# DongHoInternet.net
KiCad netlist of a schematic drawn in Altium Designer
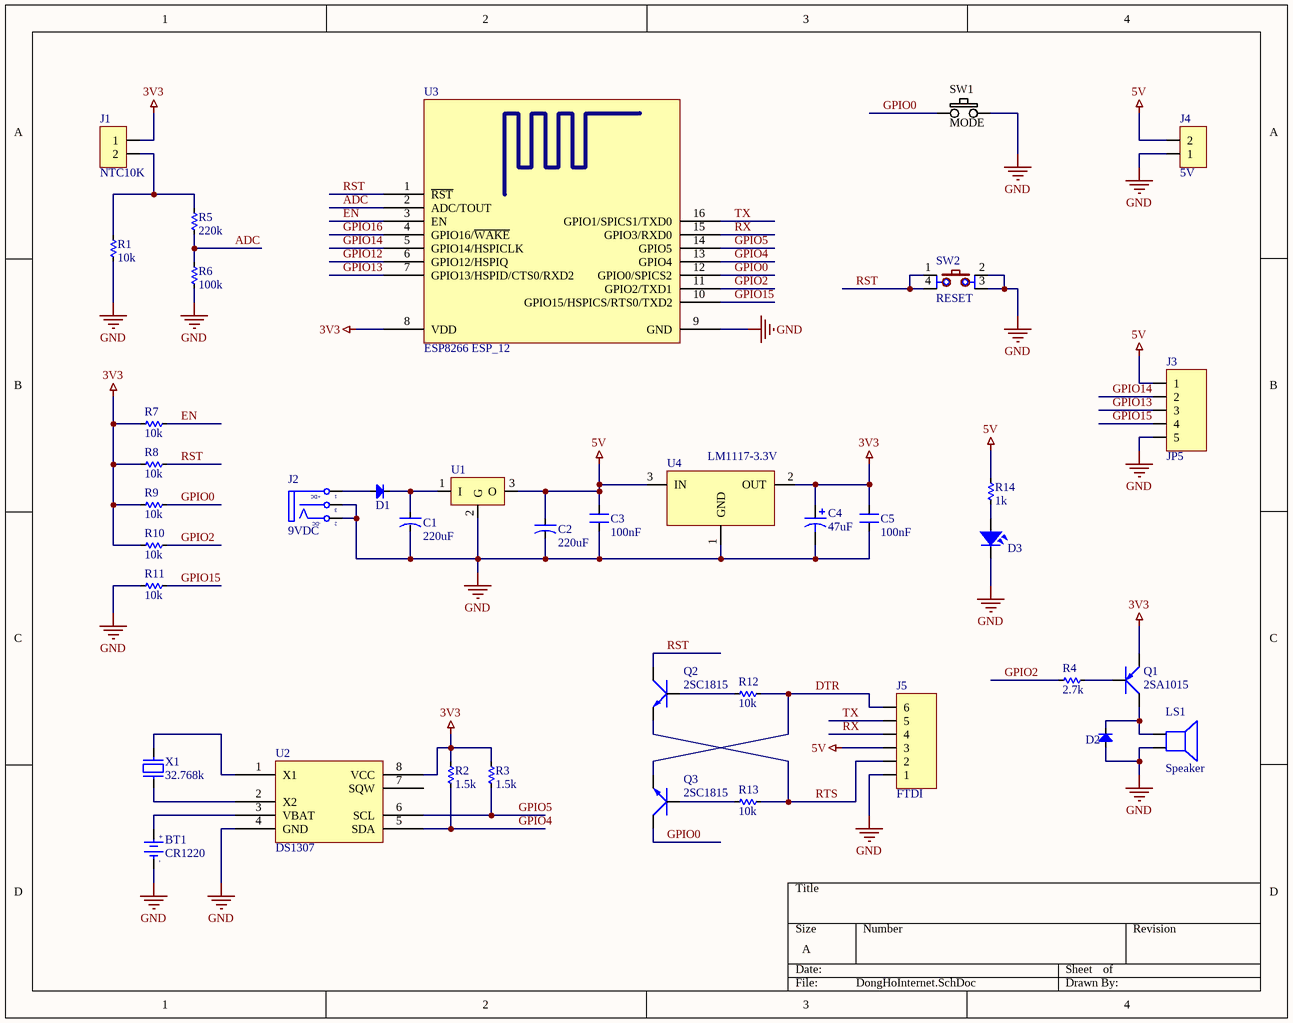
[diagram p0: DongHoInternet.SchDoc]

(export (version "E")
  (design (tool "Eeschema 10.0.6"))
  (components
    (comp (ref "BT1") (value "CR1220") (footprint "PIN CR1220") (libsource (lib "User1") (part "PIN CR1220")))
    (comp (ref "C1")
      (value "220uF")
      (footprint "CA-ALU-8")
      (description "Capacitor (Semiconductor SIM Model)")
      (fields (field (name "PUBLISHER") "Altium Limited"))
      (libsource (lib "LIBRARY") (part "CN-ALU-DIP"))
    )
    (comp (ref "C2")
      (value "220uF")
      (footprint "CA-ALU-8")
      (description "Capacitor (Semiconductor SIM Model)")
      (fields (field (name "PUBLISHER") "Altium Limited"))
      (libsource (lib "LIBRARY") (part "CN-ALU-DIP"))
    )
    (comp (ref "C3") (value "100nF") (footprint "CN-SMD-0805") (libsource (lib "LIBRARY") (part "CN")))
    (comp (ref "C4")
      (value "47uF")
      (footprint "C5mm")
      (description "Cắm")
      (libsource (lib "THU VIEN SCH_04042017_1") (part "Tu 5mm"))
    )
    (comp (ref "C5") (value "100nF") (footprint "CN-SMD-0805") (libsource (lib "LIBRARY") (part "CN")))
    (comp (ref "D1")
      (value "Diode SMD")
      (footprint "DIO-SMD-106")
      (description "Default Diode")
      (fields (field (name "PUBLISHER") "Altium Limited"))
      (libsource (lib "LIBRARY") (part "Diode SMD"))
    )
    (comp (ref "D2")
      (value "Diode SMD")
      (footprint "DIO-SMD-106")
      (description "Default Diode")
      (fields (field (name "PUBLISHER") "Altium Limited"))
      (libsource (lib "LIBRARY") (part "Diode SMD"))
    )
    (comp (ref "D3") (value "P") (footprint "LED-0805-Yellow") (libsource (lib "LIBRARY") (part "LED SMD")))
    (comp (ref "J1")
      (value "NTC10K")
      (footprint "JP2-D1T")
      (description "WR-PHD 2.54 mm Angled Socket Header")
      (fields
        (field (name "MANUFACTURER") "Würth Elektronik eiSos GmbH")
        (field (name "PARTNO") "613002143121")
        (field (name "CREATED BY") "Karrer Zheng")
      )
      (libsource (lib "LIBRARY") (part "JP2"))
    )
    (comp (ref "J2")
      (value "9VDC")
      (footprint "DC0")
      (description "Jac DC input")
      (libsource (lib "LIBRARY") (part "DCIN"))
    )
    (comp (ref "J3")
      (value "JP5")
      (footprint "JP5-D1C")
      (description "WR-PHD 2.54 mm Angled Socket Header")
      (fields
        (field (name "MANUFACTURER") "Würth Elektronik eiSos GmbH")
        (field (name "PARTNO") "613005143121")
        (field (name "CREATED BY") "Karrer Zheng")
      )
      (libsource (lib "LIBRARY") (part "JP5"))
    )
    (comp (ref "J4")
      (value "5V")
      (footprint "JP2-D1C")
      (description "WR-PHD 2.54 mm Angled Socket Header")
      (fields
        (field (name "MANUFACTURER") "Würth Elektronik eiSos GmbH")
        (field (name "PARTNO") "613002143121")
        (field (name "CREATED BY") "Karrer Zheng")
      )
      (libsource (lib "") (part "JP2_1"))
    )
    (comp (ref "J5")
      (value "FTDI")
      (footprint "JP6-D1T")
      (description "WR-PHD 2.54 mm Angled Socket Header")
      (fields
        (field (name "MANUFACTURER") "Würth Elektronik eiSos GmbH")
        (field (name "PARTNO") "613006143121")
        (field (name "CREATED BY") "Karrer Zheng")
      )
      (libsource (lib "LIBRARY") (part "JP6"))
    )
    (comp (ref "LS1")
      (value "Speaker")
      (footprint "SPEAKER")
      (description "Loudspeaker")
      (fields (field (name "PUBLISHER") "Altium Limited"))
      (libsource (lib "LIBRARY") (part "Speaker"))
    )
    (comp (ref "Q1")
      (value "2SA1015")
      (footprint "SOT23-321")
      (description "PNP 600mW, ECB")
      (libsource (lib "LIBRARY") (part "2SA1015"))
    )
    (comp (ref "Q2")
      (value "2SC1815")
      (footprint "SOT23-321")
      (description "NPN 600mW, ECB")
      (libsource (lib "LIBRARY") (part "2SC1815"))
    )
    (comp (ref "Q3")
      (value "2SC1815")
      (footprint "SOT23-321")
      (description "NPN 600mW, ECB")
      (libsource (lib "LIBRARY") (part "2SC1815"))
    )
    (comp (ref "R1")
      (value "10k")
      (footprint "RES-SMD-0805")
      (description "Resistor")
      (fields
        (field (name "MANUFACTURER") "Generic Components")
        (field (name "PUBLISHER") "Altium Hobart Technology Centre")
      )
      (libsource (lib "LIBRARY") (part "Res-SMD"))
    )
    (comp (ref "R2")
      (value "1.5k")
      (footprint "RES-SMD-0805")
      (description "Resistor")
      (fields
        (field (name "MANUFACTURER") "Generic Components")
        (field (name "PUBLISHER") "Altium Hobart Technology Centre")
      )
      (libsource (lib "LIBRARY") (part "Res-SMD"))
    )
    (comp (ref "R3")
      (value "1.5k")
      (footprint "RES-SMD-0805")
      (description "Resistor")
      (fields
        (field (name "MANUFACTURER") "Generic Components")
        (field (name "PUBLISHER") "Altium Hobart Technology Centre")
      )
      (libsource (lib "LIBRARY") (part "Res-SMD"))
    )
    (comp (ref "R4")
      (value "2.7k")
      (footprint "RES-SMD-0805")
      (description "Resistor")
      (fields
        (field (name "MANUFACTURER") "Generic Components")
        (field (name "PUBLISHER") "Altium Hobart Technology Centre")
      )
      (libsource (lib "LIBRARY") (part "Res-SMD"))
    )
    (comp (ref "R5")
      (value "220k")
      (footprint "RES-SMD-0805")
      (description "Resistor")
      (fields
        (field (name "MANUFACTURER") "Generic Components")
        (field (name "PUBLISHER") "Altium Hobart Technology Centre")
      )
      (libsource (lib "LIBRARY") (part "Res-SMD"))
    )
    (comp (ref "R6")
      (value "100k")
      (footprint "RES-SMD-0805")
      (description "Resistor")
      (fields
        (field (name "MANUFACTURER") "Generic Components")
        (field (name "PUBLISHER") "Altium Hobart Technology Centre")
      )
      (libsource (lib "LIBRARY") (part "Res-SMD"))
    )
    (comp (ref "R7")
      (value "10k")
      (footprint "RES-SMD-0805")
      (description "Resistor")
      (fields
        (field (name "MANUFACTURER") "Generic Components")
        (field (name "PUBLISHER") "Altium Hobart Technology Centre")
      )
      (libsource (lib "LIBRARY") (part "Res-SMD"))
    )
    (comp (ref "R8")
      (value "10k")
      (footprint "RES-SMD-0805")
      (description "Resistor")
      (fields
        (field (name "MANUFACTURER") "Generic Components")
        (field (name "PUBLISHER") "Altium Hobart Technology Centre")
      )
      (libsource (lib "LIBRARY") (part "Res-SMD"))
    )
    (comp (ref "R9")
      (value "10k")
      (footprint "RES-SMD-0805")
      (description "Resistor")
      (fields
        (field (name "MANUFACTURER") "Generic Components")
        (field (name "PUBLISHER") "Altium Hobart Technology Centre")
      )
      (libsource (lib "LIBRARY") (part "Res-SMD"))
    )
    (comp (ref "R10")
      (value "10k")
      (footprint "RES-SMD-0805")
      (description "Resistor")
      (fields
        (field (name "MANUFACTURER") "Generic Components")
        (field (name "PUBLISHER") "Altium Hobart Technology Centre")
      )
      (libsource (lib "LIBRARY") (part "Res-SMD"))
    )
    (comp (ref "R11")
      (value "10k")
      (footprint "RES-SMD-0805")
      (description "Resistor")
      (fields
        (field (name "MANUFACTURER") "Generic Components")
        (field (name "PUBLISHER") "Altium Hobart Technology Centre")
      )
      (libsource (lib "LIBRARY") (part "Res-SMD"))
    )
    (comp (ref "R12")
      (value "10k")
      (footprint "RES-SMD-0805")
      (description "Resistor")
      (fields
        (field (name "MANUFACTURER") "Generic Components")
        (field (name "PUBLISHER") "Altium Hobart Technology Centre")
      )
      (libsource (lib "LIBRARY") (part "Res-SMD"))
    )
    (comp (ref "R13")
      (value "10k")
      (footprint "RES-SMD-0805")
      (description "Resistor")
      (fields
        (field (name "MANUFACTURER") "Generic Components")
        (field (name "PUBLISHER") "Altium Hobart Technology Centre")
      )
      (libsource (lib "LIBRARY") (part "Res-SMD"))
    )
    (comp (ref "R14")
      (value "1k")
      (footprint "RES-SMD-0805")
      (description "Resistor")
      (fields
        (field (name "MANUFACTURER") "Generic Components")
        (field (name "PUBLISHER") "Altium Hobart Technology Centre")
      )
      (libsource (lib "LIBRARY") (part "Res-SMD"))
    )
    (comp (ref "SW1")
      (value "MODE")
      (footprint "SW-OMRONRA-Y")
      (description "SW-D6-R / SW-DS-S / SW-14X14 / SW-7X7")
      (libsource (lib "vh_altium_library") (part "SW-PB-YELLOW-RA"))
    )
    (comp (ref "SW2")
      (value "RESET")
      (footprint "SW2-SMD")
      (description "Switch button 4 pin")
      (libsource (lib "LIBRARY") (part "SW4"))
    )
    (comp (ref "U1")
      (value "LM78xx")
      (footprint "TO252-123")
      (description "Positive Voltage Regulator")
      (fields (field (name "PUBLISHER") "Altium Limited"))
      (libsource (lib "LIBRARY") (part "LM78xx"))
    )
    (comp (ref "U2") (value "DS1307") (footprint "DS1307") (libsource (lib "User2") (part "DS1307")))
    (comp (ref "U3")
      (value "ESP8266 ESP_12")
      (footprint "ESP8266 ESP_12")
      (description "ESP8266 ESP-12")
      (fields (field (name "PUBLISHER") "Cynetik Group") (field (name "LATESTREVIEWER") "Zion Blue"))
      (libsource (lib "ESP8266") (part "ESP8266 ESP_12"))
    )
    (comp (ref "U4")
      (value "LM1117-3.3V")
      (footprint "SOT223")
      (description "800mA Low-Dropout Linear Regulator")
      (fields (field (name "CREATOR") "Nguyen Ba Bien"))
      (libsource (lib "LIBRARY") (part "LM1117"))
    )
    (comp (ref "X1")
      (value "32.768k")
      (footprint "XT32k")
      (description "Crystal, 32.768 KHz, -40 to 85 degC, 3.2 x 1.5 x 0.9 mm SMD")
      (libsource (lib "LIBRARY") (part "XT2"))
    )
  )
  (nets
    (net (code "1") (name "/ADC") (class "Default")
      (node (ref "R5") (pin "2") (pinfunction "2_2") (pintype "passive"))
      (node (ref "R6") (pin "1") (pinfunction "1_1") (pintype "passive"))
      (node (ref "U3") (pin "2") (pinfunction "ADC/TOUT_2") (pintype "passive"))
    )
    (net (code "2") (name "/DTR") (class "Default")
      (node (ref "J5") (pin "6") (pinfunction "6_6") (pintype "passive"))
      (node (ref "Q3") (pin "1") (pinfunction "E_1") (pintype "passive"))
      (node (ref "R12") (pin "2") (pinfunction "2_2") (pintype "passive"))
    )
    (net (code "3") (name "/EN") (class "Default")
      (node (ref "R7") (pin "2") (pinfunction "2_2") (pintype "passive"))
      (node (ref "U3") (pin "3") (pinfunction "EN_3") (pintype "passive"))
    )
    (net (code "4") (name "/GPIO0") (class "Default")
      (node (ref "Q3") (pin "2") (pinfunction "C_2") (pintype "passive"))
      (node (ref "R9") (pin "2") (pinfunction "2_2") (pintype "passive"))
      (node (ref "SW1") (pin "2") (pintype "passive"))
      (node (ref "U3") (pin "12") (pinfunction "GPIO0/SPICS2_12") (pintype "passive"))
    )
    (net (code "5") (name "/GPIO2") (class "Default")
      (node (ref "R10") (pin "2") (pinfunction "2_2") (pintype "passive"))
      (node (ref "R4") (pin "1") (pinfunction "1_1") (pintype "passive"))
      (node (ref "U3") (pin "11") (pinfunction "GPIO2/TXD1_11") (pintype "passive"))
    )
    (net (code "6") (name "/GPIO4") (class "Default")
      (node (ref "R2") (pin "2") (pinfunction "2_2") (pintype "passive"))
      (node (ref "U2") (pin "5") (pinfunction "SDA_5") (pintype "passive"))
      (node (ref "U3") (pin "13") (pinfunction "GPIO4_13") (pintype "passive"))
    )
    (net (code "7") (name "/GPIO5") (class "Default")
      (node (ref "R3") (pin "2") (pinfunction "2_2") (pintype "passive"))
      (node (ref "U2") (pin "6") (pinfunction "SCL_6") (pintype "passive"))
      (node (ref "U3") (pin "14") (pinfunction "GPIO5_14") (pintype "passive"))
    )
    (net (code "8") (name "/GPIO12") (class "Default")
      (node (ref "U3") (pin "6") (pinfunction "GPIO12/HSPIQ_6") (pintype "passive"))
    )
    (net (code "9") (name "/GPIO13") (class "Default")
      (node (ref "J3") (pin "3") (pinfunction "3_3") (pintype "passive"))
      (node (ref "U3") (pin "7") (pinfunction "GPIO13/HSPID/CTS0/RXD2_7") (pintype "passive"))
    )
    (net (code "10") (name "/GPIO14") (class "Default")
      (node (ref "J3") (pin "2") (pinfunction "2_2") (pintype "passive"))
      (node (ref "U3") (pin "5") (pinfunction "GPIO14/HSPICLK_5") (pintype "passive"))
    )
    (net (code "11") (name "/GPIO15") (class "Default")
      (node (ref "J3") (pin "4") (pinfunction "4_4") (pintype "passive"))
      (node (ref "R11") (pin "2") (pinfunction "2_2") (pintype "passive"))
      (node (ref "U3") (pin "10") (pinfunction "GPIO15/HSPICS/RTS0/TXD2_10") (pintype "passive"))
    )
    (net (code "12") (name "/GPIO16") (class "Default")
      (node (ref "U3") (pin "4") (pinfunction "GPIO16/~{WAKE}_4") (pintype "passive"))
    )
    (net (code "13") (name "/RST") (class "Default")
      (node (ref "Q2") (pin "2") (pinfunction "C_2") (pintype "passive"))
      (node (ref "R8") (pin "2") (pinfunction "2_2") (pintype "passive"))
      (node (ref "SW2") (pin "1") (pintype "passive"))
      (node (ref "SW2") (pin "4") (pinfunction "4_4") (pintype "passive"))
      (node (ref "U3") (pin "1") (pinfunction "~{RST}_1") (pintype "passive"))
    )
    (net (code "14") (name "/RTS") (class "Default")
      (node (ref "J5") (pin "2") (pinfunction "2_2") (pintype "passive"))
      (node (ref "Q2") (pin "1") (pinfunction "E_1") (pintype "passive"))
      (node (ref "R13") (pin "2") (pinfunction "2_2") (pintype "passive"))
    )
    (net (code "15") (name "/RX") (class "Default")
      (node (ref "J5") (pin "4") (pinfunction "4_4") (pintype "passive"))
      (node (ref "U3") (pin "15") (pinfunction "GPIO3/RXD0_15") (pintype "passive"))
    )
    (net (code "16") (name "/TX") (class "Default")
      (node (ref "J5") (pin "5") (pinfunction "5_5") (pintype "passive"))
      (node (ref "U3") (pin "16") (pinfunction "GPIO1/SPICS1/TXD0_16") (pintype "passive"))
    )
    (net (code "17") (name "3V3") (class "Default")
      (node (ref "C4") (pin "1") (pinfunction "1_1") (pintype "passive"))
      (node (ref "C5") (pin "2") (pinfunction "2_2") (pintype "passive"))
      (node (ref "J1") (pin "1") (pinfunction "1_1") (pintype "passive"))
      (node (ref "Q1") (pin "1") (pinfunction "E_1") (pintype "passive"))
      (node (ref "R10") (pin "1") (pinfunction "1_1") (pintype "passive"))
      (node (ref "R2") (pin "1") (pinfunction "1_1") (pintype "passive"))
      (node (ref "R3") (pin "1") (pinfunction "1_1") (pintype "passive"))
      (node (ref "R7") (pin "1") (pinfunction "1_1") (pintype "passive"))
      (node (ref "R8") (pin "1") (pinfunction "1_1") (pintype "passive"))
      (node (ref "R9") (pin "1") (pinfunction "1_1") (pintype "passive"))
      (node (ref "U2") (pin "8") (pinfunction "VCC_8") (pintype "passive"))
      (node (ref "U3") (pin "8") (pinfunction "VDD_8") (pintype "passive"))
      (node (ref "U4") (pin "2") (pinfunction "OUT_2") (pintype "passive"))
    )
    (net (code "18") (name "5V") (class "Default")
      (node (ref "C2") (pin "1") (pinfunction "1_1") (pintype "passive"))
      (node (ref "C3") (pin "2") (pinfunction "2_2") (pintype "passive"))
      (node (ref "J3") (pin "1") (pinfunction "1_1") (pintype "passive"))
      (node (ref "J4") (pin "2") (pinfunction "2_2") (pintype "passive"))
      (node (ref "J5") (pin "3") (pinfunction "3_3") (pintype "passive"))
      (node (ref "R14") (pin "2") (pinfunction "2_2") (pintype "passive"))
      (node (ref "U1") (pin "3") (pinfunction "O_3") (pintype "power_in"))
      (node (ref "U4") (pin "3") (pinfunction "IN_3") (pintype "passive"))
    )
    (net (code "19") (name "GND") (class "Default")
      (node (ref "BT1") (pin "2") (pinfunction "GND_2") (pintype "passive"))
      (node (ref "C1") (pin "2") (pinfunction "2_2") (pintype "passive"))
      (node (ref "C2") (pin "2") (pinfunction "2_2") (pintype "passive"))
      (node (ref "C3") (pin "1") (pinfunction "1_1") (pintype "passive"))
      (node (ref "C4") (pin "2") (pinfunction "2_2") (pintype "passive"))
      (node (ref "C5") (pin "1") (pinfunction "1_1") (pintype "passive"))
      (node (ref "D2") (pin "1") (pinfunction "A_1") (pintype "passive"))
      (node (ref "D3") (pin "2") (pinfunction "2_2") (pintype "passive"))
      (node (ref "J2") (pin "2") (pinfunction "TN_2") (pintype "passive"))
      (node (ref "J2") (pin "3") (pinfunction "S_3") (pintype "power_in"))
      (node (ref "J3") (pin "5") (pinfunction "5_5") (pintype "passive"))
      (node (ref "J4") (pin "1") (pinfunction "1_1") (pintype "passive"))
      (node (ref "J5") (pin "1") (pinfunction "1_1") (pintype "passive"))
      (node (ref "LS1") (pin "2") (pinfunction "2_2") (pintype "passive"))
      (node (ref "R1") (pin "2") (pinfunction "2_2") (pintype "passive"))
      (node (ref "R11") (pin "1") (pinfunction "1_1") (pintype "passive"))
      (node (ref "R6") (pin "2") (pinfunction "2_2") (pintype "passive"))
      (node (ref "SW1") (pin "1") (pintype "passive"))
      (node (ref "SW2") (pin "2") (pinfunction "2_2") (pintype "passive"))
      (node (ref "SW2") (pin "3") (pinfunction "3_3") (pintype "passive"))
      (node (ref "U1") (pin "2") (pinfunction "G_2") (pintype "power_in"))
      (node (ref "U2") (pin "4") (pinfunction "GND_4") (pintype "passive"))
      (node (ref "U3") (pin "9") (pinfunction "GND_9") (pintype "passive"))
      (node (ref "U4") (pin "1") (pinfunction "GND_1") (pintype "passive"))
    )
    (net (code "20") (name "Net-(BT1-+3V)") (class "Default")
      (node (ref "BT1") (pin "1") (pinfunction "+3V_1") (pintype "passive"))
      (node (ref "U2") (pin "3") (pinfunction "VBAT_3") (pintype "passive"))
    )
    (net (code "21") (name "Net-(D1-A)") (class "Default")
      (node (ref "D1") (pin "1") (pinfunction "A_1") (pintype "passive"))
      (node (ref "J2") (pin "1") (pinfunction "T_1") (pintype "passive"))
    )
    (net (code "22") (name "Net-(D1-K)") (class "Default")
      (node (ref "C1") (pin "1") (pinfunction "1_1") (pintype "passive"))
      (node (ref "D1") (pin "2") (pinfunction "K_2") (pintype "passive"))
      (node (ref "U1") (pin "1") (pinfunction "I_1") (pintype "power_in"))
    )
    (net (code "23") (name "Net-(D2-K)") (class "Default")
      (node (ref "D2") (pin "2") (pinfunction "K_2") (pintype "passive"))
      (node (ref "LS1") (pin "1") (pinfunction "1_1") (pintype "passive"))
      (node (ref "Q1") (pin "2") (pinfunction "C_2") (pintype "passive"))
    )
    (net (code "24") (name "Net-(D3-Pad1)") (class "Default")
      (node (ref "D3") (pin "1") (pinfunction "1_1") (pintype "passive"))
      (node (ref "R14") (pin "1") (pinfunction "1_1") (pintype "passive"))
    )
    (net (code "25") (name "Net-(J1-Pad2)") (class "Default")
      (node (ref "J1") (pin "2") (pinfunction "2_2") (pintype "passive"))
      (node (ref "R1") (pin "1") (pinfunction "1_1") (pintype "passive"))
      (node (ref "R5") (pin "1") (pinfunction "1_1") (pintype "passive"))
    )
    (net (code "26") (name "Net-(Q1-B)") (class "Default")
      (node (ref "Q1") (pin "3") (pinfunction "B_3") (pintype "passive"))
      (node (ref "R4") (pin "2") (pinfunction "2_2") (pintype "passive"))
    )
    (net (code "27") (name "Net-(Q2-B)") (class "Default")
      (node (ref "Q2") (pin "3") (pinfunction "B_3") (pintype "passive"))
      (node (ref "R12") (pin "1") (pinfunction "1_1") (pintype "passive"))
    )
    (net (code "28") (name "Net-(Q3-B)") (class "Default")
      (node (ref "Q3") (pin "3") (pinfunction "B_3") (pintype "passive"))
      (node (ref "R13") (pin "1") (pinfunction "1_1") (pintype "passive"))
    )
    (net (code "29") (name "Net-(U2-X1)") (class "Default")
      (node (ref "U2") (pin "1") (pinfunction "X1_1") (pintype "passive"))
      (node (ref "X1") (pin "1") (pinfunction "1_1") (pintype "passive"))
    )
    (net (code "30") (name "Net-(U2-X2)") (class "Default")
      (node (ref "U2") (pin "2") (pinfunction "X2_2") (pintype "passive"))
      (node (ref "X1") (pin "2") (pinfunction "2_2") (pintype "passive"))
    )
    (net (code "31") (name "unconnected-(U2-SQW-Pad7)") (class "Default")
      (node (ref "U2") (pin "7") (pinfunction "SQW_7") (pintype "passive"))
    )
  )
)
